# raspi3_nonHatv2.net
KiCad netlist of a schematic drawn in EAGLE
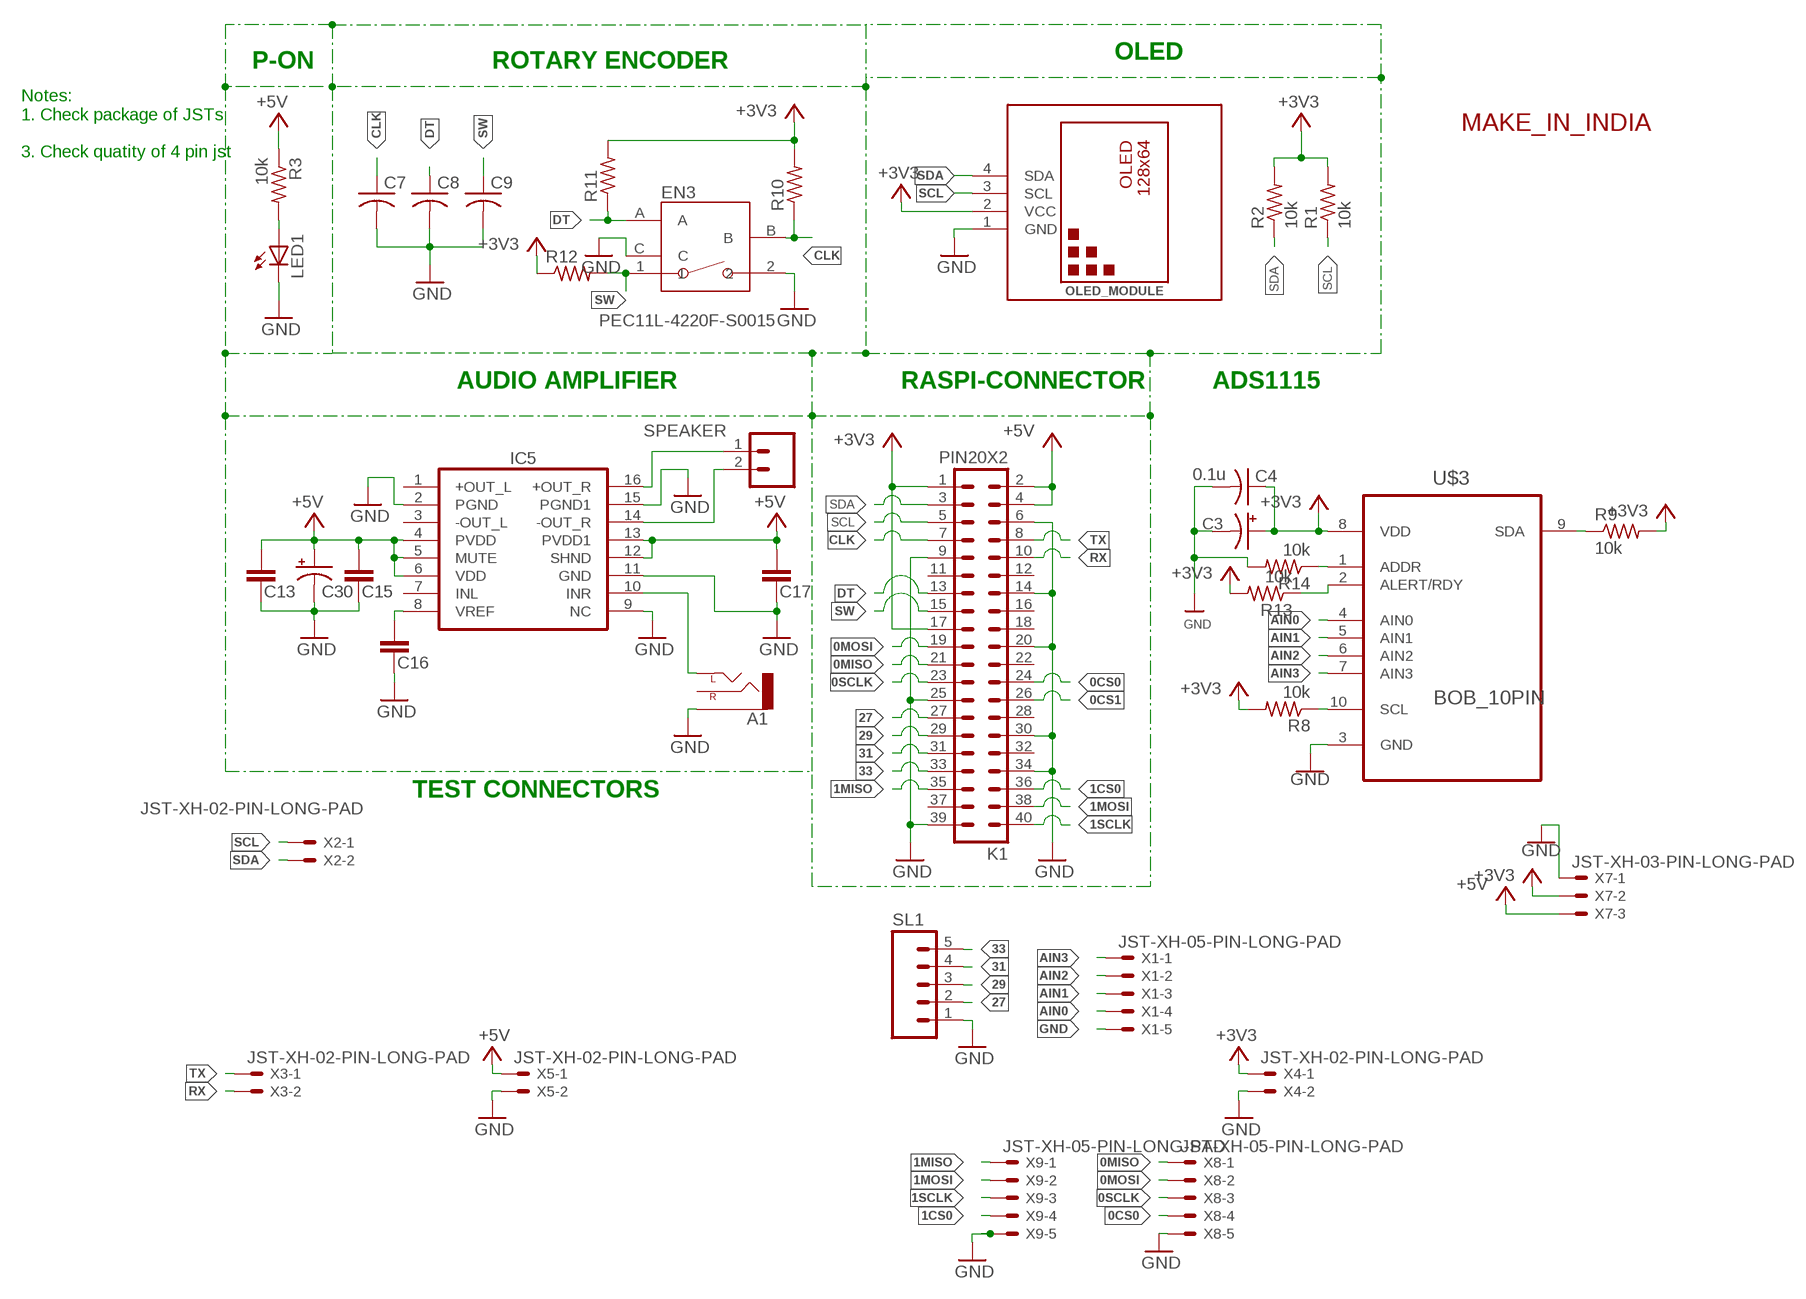
[diagram p0: schematic, sheet 1]

(export (version "E")
  (design (tool "Eeschema 10.0.6"))
  (components
    (comp (ref "A1")
      (value "AUDIO-JACKPTH")
      (footprint "eagle-import:AUDIO-JACK")
      (libsource (lib "eagle-import") (part "AUDIO-JACKPTH"))
    )
    (comp (ref "C3")
      (value "10u")
      (footprint "eagle-import:C_6032-28R")
      (libsource (lib "eagle-import") (part "CAP_POL_10V"))
    )
    (comp (ref "C4")
      (value "0.1u")
      (footprint "eagle-import:C0805")
      (libsource (lib "eagle-import") (part "CAP0805"))
    )
    (comp (ref "C7")
      (value "C-USC0603K")
      (footprint "eagle-import:C0603K")
      (libsource (lib "eagle-import") (part "C-USC0603K"))
    )
    (comp (ref "C8")
      (value "C-USC0603K")
      (footprint "eagle-import:C0603K")
      (libsource (lib "eagle-import") (part "C-USC0603K"))
    )
    (comp (ref "C9")
      (value "C-USC0603K")
      (footprint "eagle-import:C0603K")
      (libsource (lib "eagle-import") (part "C-USC0603K"))
    )
    (comp (ref "C13")
      (value "1uf")
      (footprint "eagle-import:C1206")
      (libsource (lib "eagle-import") (part "C-EUC1206"))
    )
    (comp (ref "C15")
      (value "1uf")
      (footprint "eagle-import:C1206")
      (libsource (lib "eagle-import") (part "C-EUC1206"))
    )
    (comp (ref "C16")
      (value "0.1uf")
      (footprint "eagle-import:C1206")
      (libsource (lib "eagle-import") (part "C-EUC1206"))
    )
    (comp (ref "C17")
      (value "1uf")
      (footprint "eagle-import:C1206")
      (libsource (lib "eagle-import") (part "C-EUC1206"))
    )
    (comp (ref "C30")
      (value "CAP_POL_10V")
      (footprint "eagle-import:C_6032-28R")
      (libsource (lib "eagle-import") (part "CEDT_SEPTEMBER_V2_CAP_POL_10V"))
    )
    (comp (ref "EN3")
      (value "PEC11L-4220F-S0015")
      (footprint "eagle-import:PEC11L-4220F-S0015")
      (fields
        (field (name "DIGIKEY_PARTNO") "PEC11L-4220F-S0015-ND")
        (field (name "MANUFACTURER") "Bourns Inc.")
        (field (name "CREATED_BY") "PCBLayout.com")
      )
      (libsource (lib "eagle-import") (part "PEC11L-4220F-S0015"))
    )
    (comp (ref "IC5")
      (value "PAM8403")
      (footprint "eagle-import:SOP-16")
      (libsource (lib "eagle-import") (part "PAM8403"))
    )
    (comp (ref "K1")
      (value "PIN20X2")
      (footprint "eagle-import:PIN_20X2")
      (libsource (lib "eagle-import") (part "PIN20X2"))
    )
    (comp (ref "LED1")
      (value "LED3MM")
      (footprint "eagle-import:LED3MM")
      (libsource (lib "eagle-import") (part "LED3MM"))
    )
    (comp (ref "OLED_MODULE")
      (value "DIY-MODULES_DISPLAY-OLED-128X64-I2C")
      (footprint "eagle-import:DIY-MODULES_DISPLAY-OLED-128X64-I2C")
      (libsource (lib "eagle-import") (part "DIY-MODULES_DISPLAY-OLED-128X64-I2C"))
    )
    (comp (ref "R1")
      (value "10k")
      (footprint "eagle-import:0207_7")
      (libsource (lib "eagle-import") (part "RESISTOR0207/7"))
    )
    (comp (ref "R2")
      (value "10k")
      (footprint "eagle-import:0207_7")
      (libsource (lib "eagle-import") (part "RESISTOR0207/7"))
    )
    (comp (ref "R3")
      (value "10k")
      (footprint "eagle-import:0207_7")
      (libsource (lib "eagle-import") (part "RESISTOR0207/7"))
    )
    (comp (ref "R8")
      (value "10k")
      (footprint "eagle-import:R0603")
      (libsource (lib "eagle-import") (part "CEDT_JANUARY_2015_v5_RESISTOR0603"))
    )
    (comp (ref "R9")
      (value "10k")
      (footprint "eagle-import:R0603")
      (libsource (lib "eagle-import") (part "CEDT_JANUARY_2015_v5_RESISTOR0603"))
    )
    (comp (ref "R10")
      (value "R-US_M0805")
      (footprint "eagle-import:M0805")
      (libsource (lib "eagle-import") (part "R-US_M0805"))
    )
    (comp (ref "R11")
      (value "R-US_M0805")
      (footprint "eagle-import:M0805")
      (libsource (lib "eagle-import") (part "R-US_M0805"))
    )
    (comp (ref "R12")
      (value "R-US_M0805")
      (footprint "eagle-import:M0805")
      (libsource (lib "eagle-import") (part "R-US_M0805"))
    )
    (comp (ref "R13")
      (value "10k")
      (footprint "eagle-import:R0603")
      (libsource (lib "eagle-import") (part "CEDT_JANUARY_2015_v5_RESISTOR0603"))
    )
    (comp (ref "R14")
      (value "10k")
      (footprint "eagle-import:R0603")
      (libsource (lib "eagle-import") (part "CEDT_JANUARY_2015_v5_RESISTOR0603"))
    )
    (comp (ref "SL1")
      (value "M05")
      (footprint "eagle-import:05P")
      (libsource (lib "eagle-import") (part "M05"))
    )
    (comp (ref "SPEAKER")
      (value "M02")
      (footprint "eagle-import:02P")
      (libsource (lib "eagle-import") (part "M02"))
    )
    (comp (ref "U$1")
      (value "MAKE-IN-INDIA-LOGO")
      (footprint "eagle-import:MAKE-IN-INDIA")
      (libsource (lib "eagle-import") (part "MAKE-IN-INDIA-LOGO"))
    )
    (comp (ref "U$3")
      (value "BOB_10PIN")
      (footprint "eagle-import:BOB10")
      (libsource (lib "eagle-import") (part "BOB_10PIN"))
    )
    (comp (ref "X1")
      (value "JST-XH-05-PIN-LONG-PAD")
      (footprint "eagle-import:JST-XH-05-PACKAGE-LONG-PAD")
      (libsource (lib "eagle-import") (part "JST-XH-05-PIN-LONG-PAD"))
    )
    (comp (ref "X2")
      (value "JST-XH-02-PIN-LONG-PAD")
      (footprint "eagle-import:JST-XH-02-PACKAGE-LONG-PAD")
      (libsource (lib "eagle-import") (part "JST-XH-02-PIN-LONG-PAD"))
    )
    (comp (ref "X3")
      (value "JST-XH-02-PIN-LONG-PAD")
      (footprint "eagle-import:JST-XH-02-PACKAGE-LONG-PAD")
      (libsource (lib "eagle-import") (part "JST-XH-02-PIN-LONG-PAD"))
    )
    (comp (ref "X4")
      (value "JST-XH-02-PIN-LONG-PAD")
      (footprint "eagle-import:JST-XH-02-PACKAGE-LONG-PAD")
      (libsource (lib "eagle-import") (part "JST-XH-02-PIN-LONG-PAD"))
    )
    (comp (ref "X5")
      (value "JST-XH-02-PIN-LONG-PAD")
      (footprint "eagle-import:JST-XH-02-PACKAGE-LONG-PAD")
      (libsource (lib "eagle-import") (part "JST-XH-02-PIN-LONG-PAD"))
    )
    (comp (ref "X7")
      (value "JST-XH-03-PIN-LONG-PAD")
      (footprint "eagle-import:JST-XH-03-PACKAGE-LONG-PAD")
      (libsource (lib "eagle-import") (part "JST-XH-03-PIN-LONG-PAD"))
    )
    (comp (ref "X8")
      (value "JST-XH-05-PIN-LONG-PAD")
      (footprint "eagle-import:JST-XH-05-PACKAGE-LONG-PAD")
      (libsource (lib "eagle-import") (part "JST-XH-05-PIN-LONG-PAD"))
    )
    (comp (ref "X9")
      (value "JST-XH-05-PIN-LONG-PAD")
      (footprint "eagle-import:JST-XH-05-PACKAGE-LONG-PAD")
      (libsource (lib "eagle-import") (part "JST-XH-05-PIN-LONG-PAD"))
    )
  )
  (nets
    (net (code "1") (name "+3V3") (class "Default")
      (node (ref "C3") (pin "+") (pinfunction "+_+") (pintype "passive"))
      (node (ref "C4") (pin "1") (pinfunction "1_1") (pintype "passive"))
      (node (ref "K1") (pin "1") (pinfunction "1_1") (pintype "passive"))
      (node (ref "K1") (pin "17") (pinfunction "17_17") (pintype "passive"))
      (node (ref "OLED_MODULE") (pin "2") (pinfunction "VCC_2") (pintype "power_in"))
      (node (ref "R1") (pin "2") (pinfunction "2_2") (pintype "passive"))
      (node (ref "R10") (pin "2") (pinfunction "2_2") (pintype "passive"))
      (node (ref "R11") (pin "2") (pinfunction "2_2") (pintype "passive"))
      (node (ref "R12") (pin "1") (pinfunction "1_1") (pintype "passive"))
      (node (ref "R13") (pin "2") (pinfunction "2_2") (pintype "passive"))
      (node (ref "R2") (pin "2") (pinfunction "2_2") (pintype "passive"))
      (node (ref "R8") (pin "2") (pinfunction "2_2") (pintype "passive"))
      (node (ref "R9") (pin "2") (pinfunction "2_2") (pintype "passive"))
      (node (ref "U$3") (pin "8") (pinfunction "VDD_8") (pintype "power_in"))
      (node (ref "X4") (pin "1") (pinfunction "S_1") (pintype "passive"))
      (node (ref "X7") (pin "2") (pinfunction "S_2") (pintype "passive"))
    )
    (net (code "2") (name "+5V") (class "Default")
      (node (ref "C13") (pin "1") (pinfunction "1_1") (pintype "passive"))
      (node (ref "C15") (pin "2") (pinfunction "2_2") (pintype "passive"))
      (node (ref "C17") (pin "2") (pinfunction "2_2") (pintype "passive"))
      (node (ref "C30") (pin "+") (pinfunction "+_+") (pintype "passive"))
      (node (ref "IC5") (pin "12") (pinfunction "SHND_12") (pintype "output"))
      (node (ref "IC5") (pin "13") (pinfunction "PVDD1_13") (pintype "output"))
      (node (ref "IC5") (pin "4") (pinfunction "PVDD_4") (pintype "input"))
      (node (ref "IC5") (pin "5") (pinfunction "MUTE_5") (pintype "input"))
      (node (ref "IC5") (pin "6") (pinfunction "VDD_6") (pintype "input"))
      (node (ref "K1") (pin "2") (pinfunction "2_2") (pintype "passive"))
      (node (ref "K1") (pin "4") (pinfunction "4_4") (pintype "passive"))
      (node (ref "R3") (pin "1") (pinfunction "1_1") (pintype "passive"))
      (node (ref "X5") (pin "1") (pinfunction "S_1") (pintype "passive"))
      (node (ref "X7") (pin "3") (pinfunction "S_3") (pintype "passive"))
    )
    (net (code "3") (name "0CS0") (class "Default")
      (node (ref "K1") (pin "24") (pinfunction "24_24") (pintype "passive"))
      (node (ref "X8") (pin "4") (pinfunction "S_4") (pintype "passive"))
    )
    (net (code "4") (name "0CS1") (class "Default")
      (node (ref "K1") (pin "26") (pinfunction "26_26") (pintype "passive"))
    )
    (net (code "5") (name "0MISO") (class "Default")
      (node (ref "K1") (pin "21") (pinfunction "21_21") (pintype "passive"))
      (node (ref "X8") (pin "1") (pinfunction "S_1") (pintype "passive"))
    )
    (net (code "6") (name "0MOSI") (class "Default")
      (node (ref "K1") (pin "19") (pinfunction "19_19") (pintype "passive"))
      (node (ref "X8") (pin "2") (pinfunction "S_2") (pintype "passive"))
    )
    (net (code "7") (name "0SCLK") (class "Default")
      (node (ref "K1") (pin "23") (pinfunction "23_23") (pintype "passive"))
      (node (ref "X8") (pin "3") (pinfunction "S_3") (pintype "passive"))
    )
    (net (code "8") (name "1CS0") (class "Default")
      (node (ref "K1") (pin "36") (pinfunction "36_36") (pintype "passive"))
      (node (ref "X9") (pin "4") (pinfunction "S_4") (pintype "passive"))
    )
    (net (code "9") (name "1MISO") (class "Default")
      (node (ref "K1") (pin "35") (pinfunction "35_35") (pintype "passive"))
      (node (ref "X9") (pin "1") (pinfunction "S_1") (pintype "passive"))
    )
    (net (code "10") (name "1MOSI") (class "Default")
      (node (ref "K1") (pin "38") (pinfunction "38_38") (pintype "passive"))
      (node (ref "X9") (pin "2") (pinfunction "S_2") (pintype "passive"))
    )
    (net (code "11") (name "1SCLK") (class "Default")
      (node (ref "K1") (pin "40") (pinfunction "40_40") (pintype "passive"))
      (node (ref "X9") (pin "3") (pinfunction "S_3") (pintype "passive"))
    )
    (net (code "12") (name "27") (class "Default")
      (node (ref "K1") (pin "27") (pinfunction "27_27") (pintype "passive"))
      (node (ref "SL1") (pin "2") (pinfunction "2_2") (pintype "passive"))
    )
    (net (code "13") (name "29") (class "Default")
      (node (ref "K1") (pin "29") (pinfunction "29_29") (pintype "passive"))
      (node (ref "SL1") (pin "3") (pinfunction "3_3") (pintype "passive"))
    )
    (net (code "14") (name "31") (class "Default")
      (node (ref "K1") (pin "31") (pinfunction "31_31") (pintype "passive"))
      (node (ref "SL1") (pin "4") (pinfunction "4_4") (pintype "passive"))
    )
    (net (code "15") (name "33") (class "Default")
      (node (ref "K1") (pin "33") (pinfunction "33_33") (pintype "passive"))
      (node (ref "SL1") (pin "5") (pinfunction "5_5") (pintype "passive"))
    )
    (net (code "16") (name "AIN0") (class "Default")
      (node (ref "U$3") (pin "4") (pinfunction "AIN0_4") (pintype "input"))
      (node (ref "X1") (pin "4") (pinfunction "S_4") (pintype "passive"))
    )
    (net (code "17") (name "AIN1") (class "Default")
      (node (ref "U$3") (pin "5") (pinfunction "AIN1_5") (pintype "input"))
      (node (ref "X1") (pin "3") (pinfunction "S_3") (pintype "passive"))
    )
    (net (code "18") (name "AIN2") (class "Default")
      (node (ref "U$3") (pin "6") (pinfunction "AIN2_6") (pintype "input"))
      (node (ref "X1") (pin "2") (pinfunction "S_2") (pintype "passive"))
    )
    (net (code "19") (name "AIN3") (class "Default")
      (node (ref "U$3") (pin "7") (pinfunction "AIN3_7") (pintype "input"))
      (node (ref "X1") (pin "1") (pinfunction "S_1") (pintype "passive"))
    )
    (net (code "20") (name "CLK") (class "Default")
      (node (ref "C7") (pin "1") (pinfunction "1_1") (pintype "passive"))
      (node (ref "EN3") (pin "B") (pinfunction "B_B") (pintype "passive"))
      (node (ref "K1") (pin "7") (pinfunction "7_7") (pintype "passive"))
      (node (ref "R10") (pin "1") (pinfunction "1_1") (pintype "passive"))
    )
    (net (code "21") (name "DT") (class "Default")
      (node (ref "C8") (pin "1") (pinfunction "1_1") (pintype "passive"))
      (node (ref "EN3") (pin "A") (pinfunction "A_A") (pintype "passive"))
      (node (ref "K1") (pin "13") (pinfunction "13_13") (pintype "passive"))
      (node (ref "R11") (pin "1") (pinfunction "1_1") (pintype "passive"))
    )
    (net (code "22") (name "GND") (class "Default")
      (node (ref "A1") (pin "SLEEVE") (pinfunction "SLEEVE_SLEEVE") (pintype "bidirectional"))
      (node (ref "C13") (pin "2") (pinfunction "2_2") (pintype "passive"))
      (node (ref "C15") (pin "1") (pinfunction "1_1") (pintype "passive"))
      (node (ref "C16") (pin "2") (pinfunction "2_2") (pintype "passive"))
      (node (ref "C17") (pin "1") (pinfunction "1_1") (pintype "passive"))
      (node (ref "C3") (pin "-") (pinfunction "-_-") (pintype "passive"))
      (node (ref "C30") (pin "-") (pinfunction "-_-") (pintype "passive"))
      (node (ref "C4") (pin "2") (pinfunction "2_2") (pintype "passive"))
      (node (ref "C7") (pin "2") (pinfunction "2_2") (pintype "passive"))
      (node (ref "C8") (pin "2") (pinfunction "2_2") (pintype "passive"))
      (node (ref "C9") (pin "2") (pinfunction "2_2") (pintype "passive"))
      (node (ref "EN3") (pin "2") (pinfunction "2_2") (pintype "passive"))
      (node (ref "EN3") (pin "C") (pinfunction "C_C") (pintype "passive"))
      (node (ref "IC5") (pin "11") (pinfunction "GND_11") (pintype "output"))
      (node (ref "IC5") (pin "15") (pinfunction "PGND1_15") (pintype "output"))
      (node (ref "IC5") (pin "2") (pinfunction "PGND_2") (pintype "input"))
      (node (ref "IC5") (pin "9") (pinfunction "NC_9") (pintype "output"))
      (node (ref "K1") (pin "14") (pinfunction "14_14") (pintype "passive"))
      (node (ref "K1") (pin "20") (pinfunction "20_20") (pintype "passive"))
      (node (ref "K1") (pin "25") (pinfunction "25_25") (pintype "passive"))
      (node (ref "K1") (pin "30") (pinfunction "30_30") (pintype "passive"))
      (node (ref "K1") (pin "34") (pinfunction "34_34") (pintype "passive"))
      (node (ref "K1") (pin "39") (pinfunction "39_39") (pintype "passive"))
      (node (ref "K1") (pin "6") (pinfunction "6_6") (pintype "passive"))
      (node (ref "K1") (pin "9") (pinfunction "9_9") (pintype "passive"))
      (node (ref "LED1") (pin "K") (pinfunction "C_K") (pintype "passive"))
      (node (ref "OLED_MODULE") (pin "1") (pinfunction "GND_1") (pintype "power_in"))
      (node (ref "R14") (pin "2") (pinfunction "2_2") (pintype "passive"))
      (node (ref "SL1") (pin "1") (pinfunction "1_1") (pintype "passive"))
      (node (ref "U$3") (pin "3") (pinfunction "GND_3") (pintype "passive"))
      (node (ref "X1") (pin "5") (pinfunction "S_5") (pintype "passive"))
      (node (ref "X4") (pin "2") (pinfunction "S_2") (pintype "passive"))
      (node (ref "X5") (pin "2") (pinfunction "S_2") (pintype "passive"))
      (node (ref "X7") (pin "1") (pinfunction "S_1") (pintype "passive"))
      (node (ref "X8") (pin "5") (pinfunction "S_5") (pintype "passive"))
      (node (ref "X9") (pin "5") (pinfunction "S_5") (pintype "passive"))
    )
    (net (code "23") (name "Net-(A1-LEFT)") (class "Default")
      (node (ref "A1") (pin "TIP") (pinfunction "LEFT_TIP") (pintype "bidirectional"))
      (node (ref "IC5") (pin "10") (pinfunction "INR_10") (pintype "output"))
    )
    (net (code "24") (name "Net-(IC5-+OUT_R)") (class "Default")
      (node (ref "IC5") (pin "16") (pinfunction "+OUT_R_16") (pintype "output"))
      (node (ref "SPEAKER") (pin "1") (pinfunction "1_1") (pintype "passive"))
    )
    (net (code "25") (name "Net-(IC5--OUT_R)") (class "Default")
      (node (ref "IC5") (pin "14") (pinfunction "-OUT_R_14") (pintype "output"))
      (node (ref "SPEAKER") (pin "2") (pinfunction "2_2") (pintype "passive"))
    )
    (net (code "26") (name "Net-(IC5-VREF)") (class "Default")
      (node (ref "C16") (pin "1") (pinfunction "1_1") (pintype "passive"))
      (node (ref "IC5") (pin "8") (pinfunction "VREF_8") (pintype "input"))
    )
    (net (code "27") (name "Net-(LED1-PadA)") (class "Default")
      (node (ref "LED1") (pin "A") (pinfunction "A_A") (pintype "passive"))
      (node (ref "R3") (pin "2") (pinfunction "2_2") (pintype "passive"))
    )
    (net (code "28") (name "Net-(U$3-ADDR)") (class "Default")
      (node (ref "R14") (pin "1") (pinfunction "1_1") (pintype "passive"))
      (node (ref "U$3") (pin "1") (pinfunction "ADDR_1") (pintype "input"))
    )
    (net (code "29") (name "Net-(U$3-ALERT{slash}RDY)") (class "Default")
      (node (ref "R13") (pin "1") (pinfunction "1_1") (pintype "passive"))
      (node (ref "U$3") (pin "2") (pinfunction "ALERT/RDY_2") (pintype "input"))
    )
    (net (code "30") (name "Net-(U$3-SCL)") (class "Default")
      (node (ref "R8") (pin "1") (pinfunction "1_1") (pintype "passive"))
      (node (ref "U$3") (pin "10") (pinfunction "SCL_10") (pintype "input"))
    )
    (net (code "31") (name "Net-(U$3-SDA)") (class "Default")
      (node (ref "R9") (pin "1") (pinfunction "1_1") (pintype "passive"))
      (node (ref "U$3") (pin "9") (pinfunction "SDA_9") (pintype "bidirectional"))
    )
    (net (code "32") (name "RX") (class "Default")
      (node (ref "K1") (pin "10") (pinfunction "10_10") (pintype "passive"))
      (node (ref "X3") (pin "2") (pinfunction "S_2") (pintype "passive"))
    )
    (net (code "33") (name "SCL") (class "Default")
      (node (ref "K1") (pin "5") (pinfunction "5_5") (pintype "passive"))
      (node (ref "OLED_MODULE") (pin "3") (pinfunction "SCL_3") (pintype "bidirectional"))
      (node (ref "R1") (pin "1") (pinfunction "1_1") (pintype "passive"))
      (node (ref "X2") (pin "1") (pinfunction "S_1") (pintype "passive"))
    )
    (net (code "34") (name "SDA") (class "Default")
      (node (ref "K1") (pin "3") (pinfunction "3_3") (pintype "passive"))
      (node (ref "OLED_MODULE") (pin "4") (pinfunction "SDA_4") (pintype "bidirectional"))
      (node (ref "R2") (pin "1") (pinfunction "1_1") (pintype "passive"))
      (node (ref "X2") (pin "2") (pinfunction "S_2") (pintype "passive"))
    )
    (net (code "35") (name "SW") (class "Default")
      (node (ref "C9") (pin "1") (pinfunction "1_1") (pintype "passive"))
      (node (ref "EN3") (pin "1") (pinfunction "1_1") (pintype "passive"))
      (node (ref "K1") (pin "15") (pinfunction "15_15") (pintype "passive"))
      (node (ref "R12") (pin "2") (pinfunction "2_2") (pintype "passive"))
    )
    (net (code "36") (name "TX") (class "Default")
      (node (ref "K1") (pin "8") (pinfunction "8_8") (pintype "passive"))
      (node (ref "X3") (pin "1") (pinfunction "S_1") (pintype "passive"))
    )
    (net (code "37") (name "unconnected-(A1-RIGHT-PadRING)") (class "Default")
      (node (ref "A1") (pin "RING") (pinfunction "RIGHT_RING") (pintype "bidirectional"))
    )
    (net (code "38") (name "unconnected-(IC5-+OUT_L-Pad1)") (class "Default")
      (node (ref "IC5") (pin "1") (pinfunction "+OUT_L_1") (pintype "input"))
    )
    (net (code "39") (name "unconnected-(IC5--OUT_L-Pad3)") (class "Default")
      (node (ref "IC5") (pin "3") (pinfunction "-OUT_L_3") (pintype "input"))
    )
    (net (code "40") (name "unconnected-(IC5-INL-Pad7)") (class "Default")
      (node (ref "IC5") (pin "7") (pinfunction "INL_7") (pintype "input"))
    )
    (net (code "41") (name "unconnected-(K1-Pad11)") (class "Default")
      (node (ref "K1") (pin "11") (pinfunction "11_11") (pintype "passive"))
    )
    (net (code "42") (name "unconnected-(K1-Pad12)") (class "Default")
      (node (ref "K1") (pin "12") (pinfunction "12_12") (pintype "passive"))
    )
    (net (code "43") (name "unconnected-(K1-Pad16)") (class "Default")
      (node (ref "K1") (pin "16") (pinfunction "16_16") (pintype "passive"))
    )
    (net (code "44") (name "unconnected-(K1-Pad18)") (class "Default")
      (node (ref "K1") (pin "18") (pinfunction "18_18") (pintype "passive"))
    )
    (net (code "45") (name "unconnected-(K1-Pad22)") (class "Default")
      (node (ref "K1") (pin "22") (pinfunction "22_22") (pintype "passive"))
    )
    (net (code "46") (name "unconnected-(K1-Pad28)") (class "Default")
      (node (ref "K1") (pin "28") (pinfunction "28_28") (pintype "passive"))
    )
    (net (code "47") (name "unconnected-(K1-Pad32)") (class "Default")
      (node (ref "K1") (pin "32") (pinfunction "32_32") (pintype "passive"))
    )
    (net (code "48") (name "unconnected-(K1-Pad37)") (class "Default")
      (node (ref "K1") (pin "37") (pinfunction "37_37") (pintype "passive"))
    )
  )
)
